# RFID-RC522-Wemos.net
KiCad netlist of a schematic drawn in EAGLE
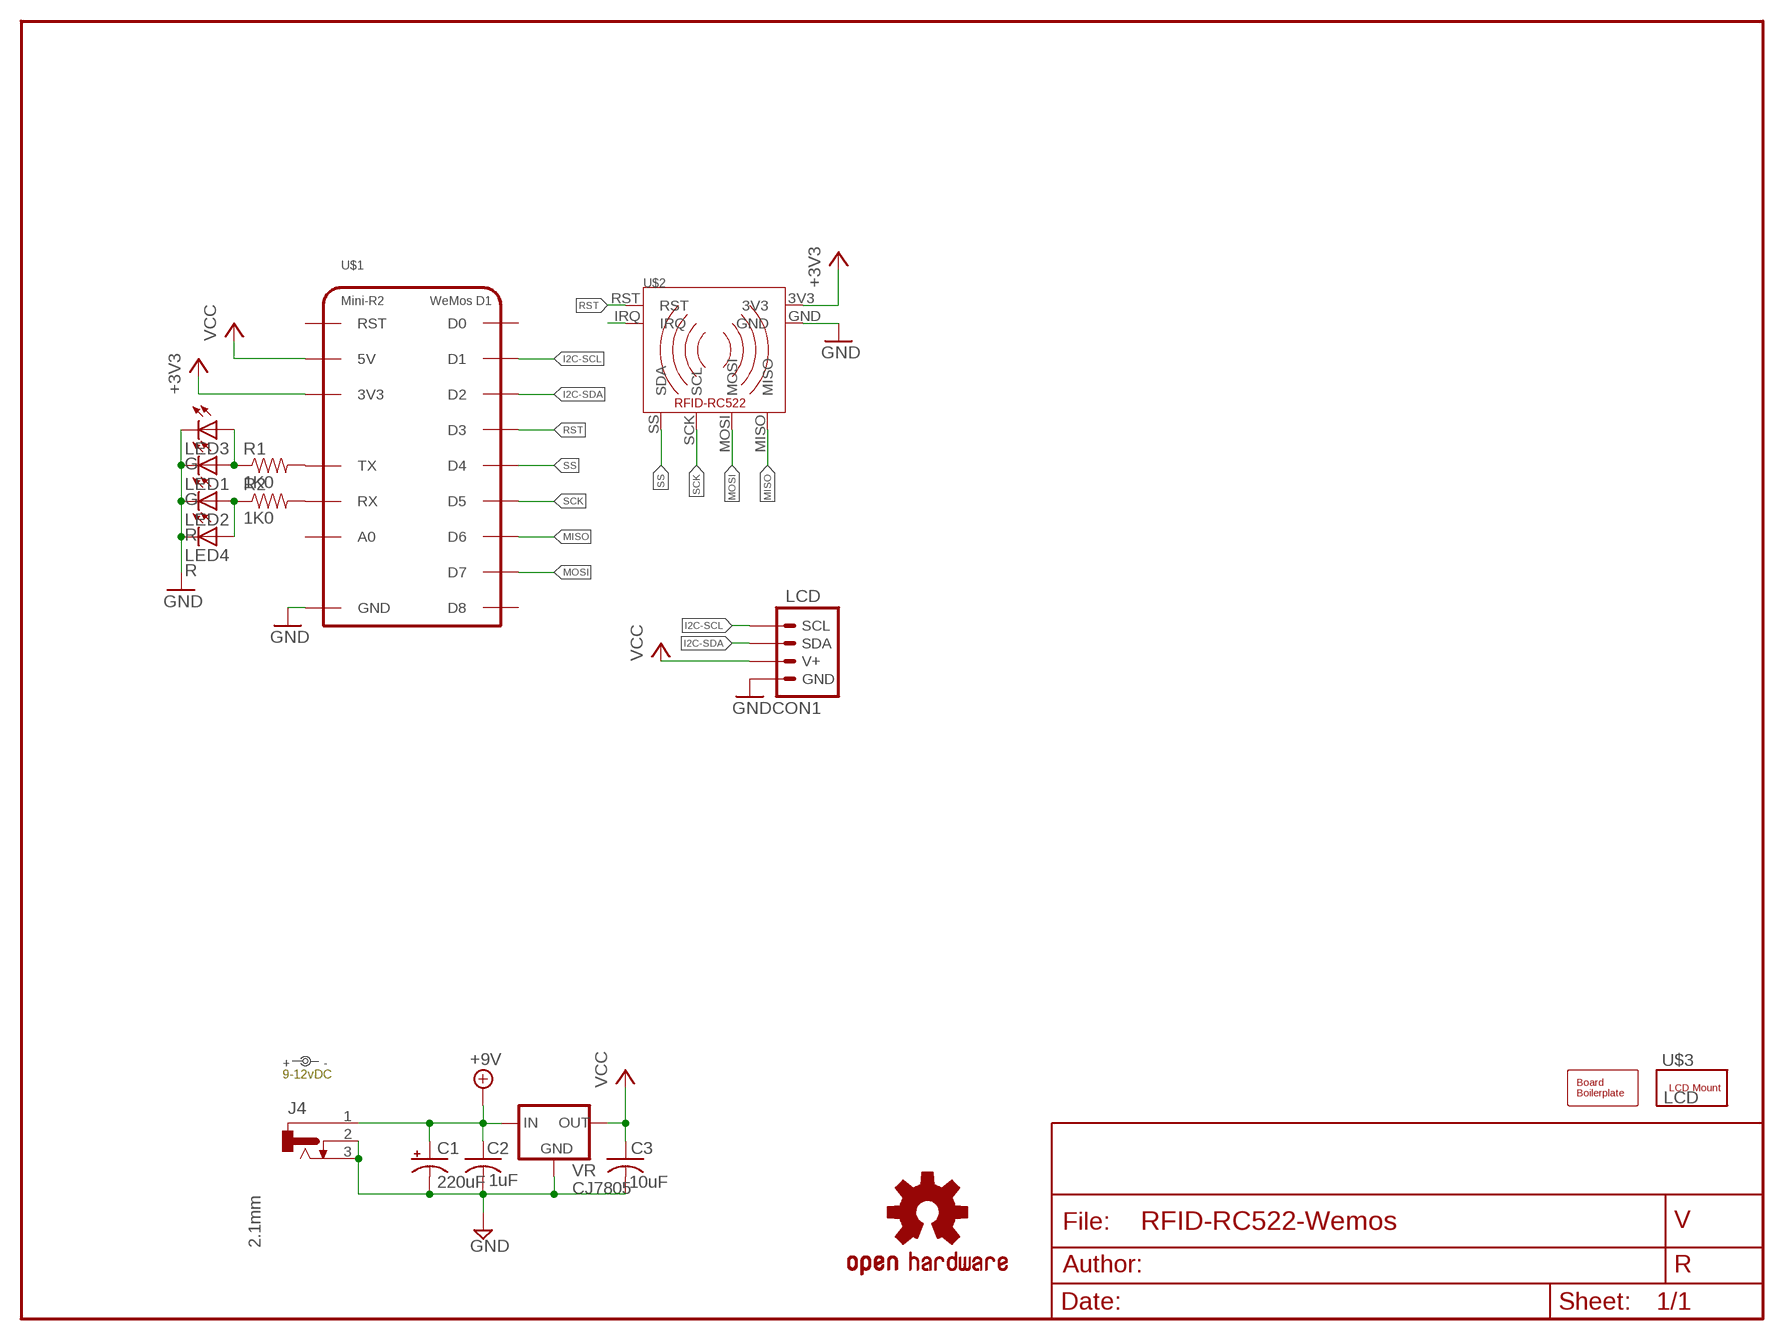
[diagram p0: schematic, sheet 1]

(export (version "E")
  (design (tool "Eeschema 10.0.6"))
  (components
    (comp (ref "BOARD1")
      (value "8x10")
      (footprint "eagle-import:BOARD-DINRAIL-3.17INX10CM")
      (libsource (lib "eagle-import") (part "BOARD80X100"))
    )
    (comp (ref "C1")
      (value "220uF")
      (footprint "eagle-import:0810-CAP")
      (libsource (lib "eagle-import") (part "CAP-POL0810"))
    )
    (comp (ref "C2")
      (value "1uF")
      (footprint "eagle-import:0603-CAP")
      (libsource (lib "eagle-import") (part "CAP0603"))
    )
    (comp (ref "C3")
      (value "10uF")
      (footprint "eagle-import:0603-CAP")
      (libsource (lib "eagle-import") (part "CAP0603"))
    )
    (comp (ref "CON1")
      (value "LCD")
      (footprint "eagle-import:I2C-L")
      (libsource (lib "eagle-import") (part "CONNECTOR-I2CLEFT"))
    )
    (comp (ref "J4")
      (value "2.1mm")
      (footprint "eagle-import:DCJ0202")
      (libsource (lib "eagle-import") (part "CONNECTOR-DC-POWER-RA"))
    )
    (comp (ref "LED1")
      (value "G")
      (footprint "eagle-import:0603-LED")
      (libsource (lib "eagle-import") (part "LED0603-LED"))
    )
    (comp (ref "LED2")
      (value "R")
      (footprint "eagle-import:0603-LED")
      (libsource (lib "eagle-import") (part "LED0603-LED"))
    )
    (comp (ref "LED3")
      (value "G")
      (footprint "eagle-import:LED5MM")
      (libsource (lib "eagle-import") (part "LEDLED5MM"))
    )
    (comp (ref "LED4")
      (value "R")
      (footprint "eagle-import:LED5MM")
      (libsource (lib "eagle-import") (part "LEDLED5MM"))
    )
    (comp (ref "LOGO1")
      (value "OSHW")
      (footprint "eagle-import:OSHW-LOGO-L")
      (libsource (lib "eagle-import") (part "DOC-OSHW-LOGOL"))
    )
    (comp (ref "POWER")
      (value "9-12vDC")
      (footprint "eagle-import:PWR_LABEL")
      (libsource (lib "eagle-import") (part "DOC-POWER_LABEL"))
    )
    (comp (ref "R1")
      (value "1K0")
      (footprint "eagle-import:0805-RES")
      (libsource (lib "eagle-import") (part "R0805-RES"))
    )
    (comp (ref "R2")
      (value "1K0")
      (footprint "eagle-import:0603-RES")
      (libsource (lib "eagle-import") (part "R0603-RES"))
    )
    (comp (ref "U$1")
      (value "Mini-R2")
      (footprint "eagle-import:WEMOS-D1")
      (libsource (lib "eagle-import") (part "WEMOS-D1V1"))
    )
    (comp (ref "U$2")
      (value "RFIDBACK")
      (footprint "eagle-import:RC522-REVERSE")
      (libsource (lib "eagle-import") (part "RFIDBACK"))
    )
    (comp (ref "U$3")
      (value "LCD")
      (footprint "eagle-import:LCD-16X2-SILK")
      (libsource (lib "eagle-import") (part "LCD1602"))
    )
    (comp (ref "VR")
      (value "CJ7805")
      (footprint "eagle-import:TO-252")
      (libsource (lib "eagle-import") (part "VREG-?-DPAK5"))
    )
  )
  (nets
    (net (code "1") (name "+3V3") (class "Default")
      (node (ref "U$1") (pin "3V3") (pinfunction "3V3_3V3") (pintype "bidirectional"))
      (node (ref "U$2") (pin "3V3") (pinfunction "3V3_3V3") (pintype "bidirectional"))
    )
    (net (code "2") (name "+9V") (class "Default")
      (node (ref "C1") (pin "+") (pinfunction "+_+") (pintype "passive"))
      (node (ref "C2") (pin "1") (pinfunction "1_1") (pintype "passive"))
      (node (ref "J4") (pin "1") (pinfunction "1_1") (pintype "passive"))
      (node (ref "VR") (pin "1") (pinfunction "IN_1") (pintype "input"))
    )
    (net (code "3") (name "GND") (class "Default")
      (node (ref "C1") (pin "-") (pinfunction "-_-") (pintype "passive"))
      (node (ref "C2") (pin "2") (pinfunction "2_2") (pintype "passive"))
      (node (ref "C3") (pin "2") (pinfunction "2_2") (pintype "passive"))
      (node (ref "CON1") (pin "GND") (pinfunction "GND_GND") (pintype "passive"))
      (node (ref "CON1") (pin "GND@1") (pinfunction "GND_GND@1") (pintype "passive"))
      (node (ref "J4") (pin "2") (pinfunction "2_2") (pintype "passive"))
      (node (ref "J4") (pin "3") (pinfunction "3_3") (pintype "passive"))
      (node (ref "LED1") (pin "C") (pinfunction "C_C") (pintype "passive"))
      (node (ref "LED2") (pin "C") (pinfunction "C_C") (pintype "passive"))
      (node (ref "LED3") (pin "K") (pinfunction "C_K") (pintype "passive"))
      (node (ref "LED4") (pin "K") (pinfunction "C_K") (pintype "passive"))
      (node (ref "U$1") (pin "GND") (pinfunction "GND_GND") (pintype "bidirectional"))
      (node (ref "U$2") (pin "GND") (pinfunction "GND_GND") (pintype "bidirectional"))
      (node (ref "VR") (pin "2") (pinfunction "GND_2") (pintype "input"))
    )
    (net (code "4") (name "I2C-SCL") (class "Default")
      (node (ref "CON1") (pin "SCL") (pinfunction "SCL_SCL") (pintype "passive"))
      (node (ref "CON1") (pin "SCL@1") (pinfunction "SCL_SCL@1") (pintype "passive"))
      (node (ref "U$1") (pin "D1") (pinfunction "D1_D1") (pintype "bidirectional"))
    )
    (net (code "5") (name "I2C-SDA") (class "Default")
      (node (ref "CON1") (pin "SDA") (pinfunction "SDA_SDA") (pintype "passive"))
      (node (ref "CON1") (pin "SDA@1") (pinfunction "SDA_SDA@1") (pintype "passive"))
      (node (ref "U$1") (pin "D2") (pinfunction "D2_D2") (pintype "bidirectional"))
    )
    (net (code "6") (name "MISO") (class "Default")
      (node (ref "U$1") (pin "D6") (pinfunction "D6_D6") (pintype "bidirectional"))
      (node (ref "U$2") (pin "MISO") (pinfunction "MISO_MISO") (pintype "bidirectional"))
    )
    (net (code "7") (name "MOSI") (class "Default")
      (node (ref "U$1") (pin "D7") (pinfunction "D7_D7") (pintype "bidirectional"))
      (node (ref "U$2") (pin "MOSI") (pinfunction "MOSI_MOSI") (pintype "bidirectional"))
    )
    (net (code "8") (name "Net-(LED1-PadA)") (class "Default")
      (node (ref "LED1") (pin "A") (pinfunction "A_A") (pintype "passive"))
      (node (ref "LED3") (pin "A") (pinfunction "A_A") (pintype "passive"))
      (node (ref "R1") (pin "1") (pinfunction "1_1") (pintype "passive"))
    )
    (net (code "9") (name "Net-(LED2-PadA)") (class "Default")
      (node (ref "LED2") (pin "A") (pinfunction "A_A") (pintype "passive"))
      (node (ref "LED4") (pin "A") (pinfunction "A_A") (pintype "passive"))
      (node (ref "R2") (pin "1") (pinfunction "1_1") (pintype "passive"))
    )
    (net (code "10") (name "Net-(R1-Pad2)") (class "Default")
      (node (ref "R1") (pin "2") (pinfunction "2_2") (pintype "passive"))
      (node (ref "U$1") (pin "TX") (pinfunction "TX_TX") (pintype "bidirectional"))
    )
    (net (code "11") (name "Net-(R2-Pad2)") (class "Default")
      (node (ref "R2") (pin "2") (pinfunction "2_2") (pintype "passive"))
      (node (ref "U$1") (pin "RX") (pinfunction "RX_RX") (pintype "bidirectional"))
    )
    (net (code "12") (name "RST") (class "Default")
      (node (ref "U$1") (pin "D3") (pinfunction "D3_D3") (pintype "bidirectional"))
      (node (ref "U$2") (pin "RST") (pinfunction "RST_RST") (pintype "bidirectional"))
    )
    (net (code "13") (name "SCK") (class "Default")
      (node (ref "U$1") (pin "D5") (pinfunction "D5_D5") (pintype "bidirectional"))
      (node (ref "U$2") (pin "SCK") (pinfunction "SCL_SCK") (pintype "bidirectional"))
    )
    (net (code "14") (name "SS") (class "Default")
      (node (ref "U$1") (pin "D4") (pinfunction "D4_D4") (pintype "bidirectional"))
      (node (ref "U$2") (pin "SS") (pinfunction "SDA_SS") (pintype "bidirectional"))
    )
    (net (code "15") (name "VCC") (class "Default")
      (node (ref "C3") (pin "1") (pinfunction "1_1") (pintype "passive"))
      (node (ref "CON1") (pin "V+") (pinfunction "V+_V+") (pintype "passive"))
      (node (ref "CON1") (pin "V+@1") (pinfunction "V+_V+@1") (pintype "passive"))
      (node (ref "U$1") (pin "5V") (pinfunction "5V_5V") (pintype "bidirectional"))
      (node (ref "VR") (pin "3") (pinfunction "OUT_3") (pintype "output"))
    )
    (net (code "16") (name "unconnected-(U$1-PadA0)") (class "Default")
      (node (ref "U$1") (pin "A0") (pinfunction "A0_A0") (pintype "bidirectional"))
    )
    (net (code "17") (name "unconnected-(U$1-PadD0)") (class "Default")
      (node (ref "U$1") (pin "D0") (pinfunction "D0_D0") (pintype "bidirectional"))
    )
    (net (code "18") (name "unconnected-(U$1-PadD8)") (class "Default")
      (node (ref "U$1") (pin "D8") (pinfunction "D8_D8") (pintype "bidirectional"))
    )
    (net (code "19") (name "unconnected-(U$1-PadRST)") (class "Default")
      (node (ref "U$1") (pin "RST") (pinfunction "RST_RST") (pintype "bidirectional"))
    )
    (net (code "20") (name "unconnected-(U$2-PadIRQ)") (class "Default")
      (node (ref "U$2") (pin "IRQ") (pinfunction "IRQ_IRQ") (pintype "bidirectional"))
    )
  )
)
